# CajitaAbierta_v06_robotique.net
KiCad netlist of a schematic drawn in EAGLE
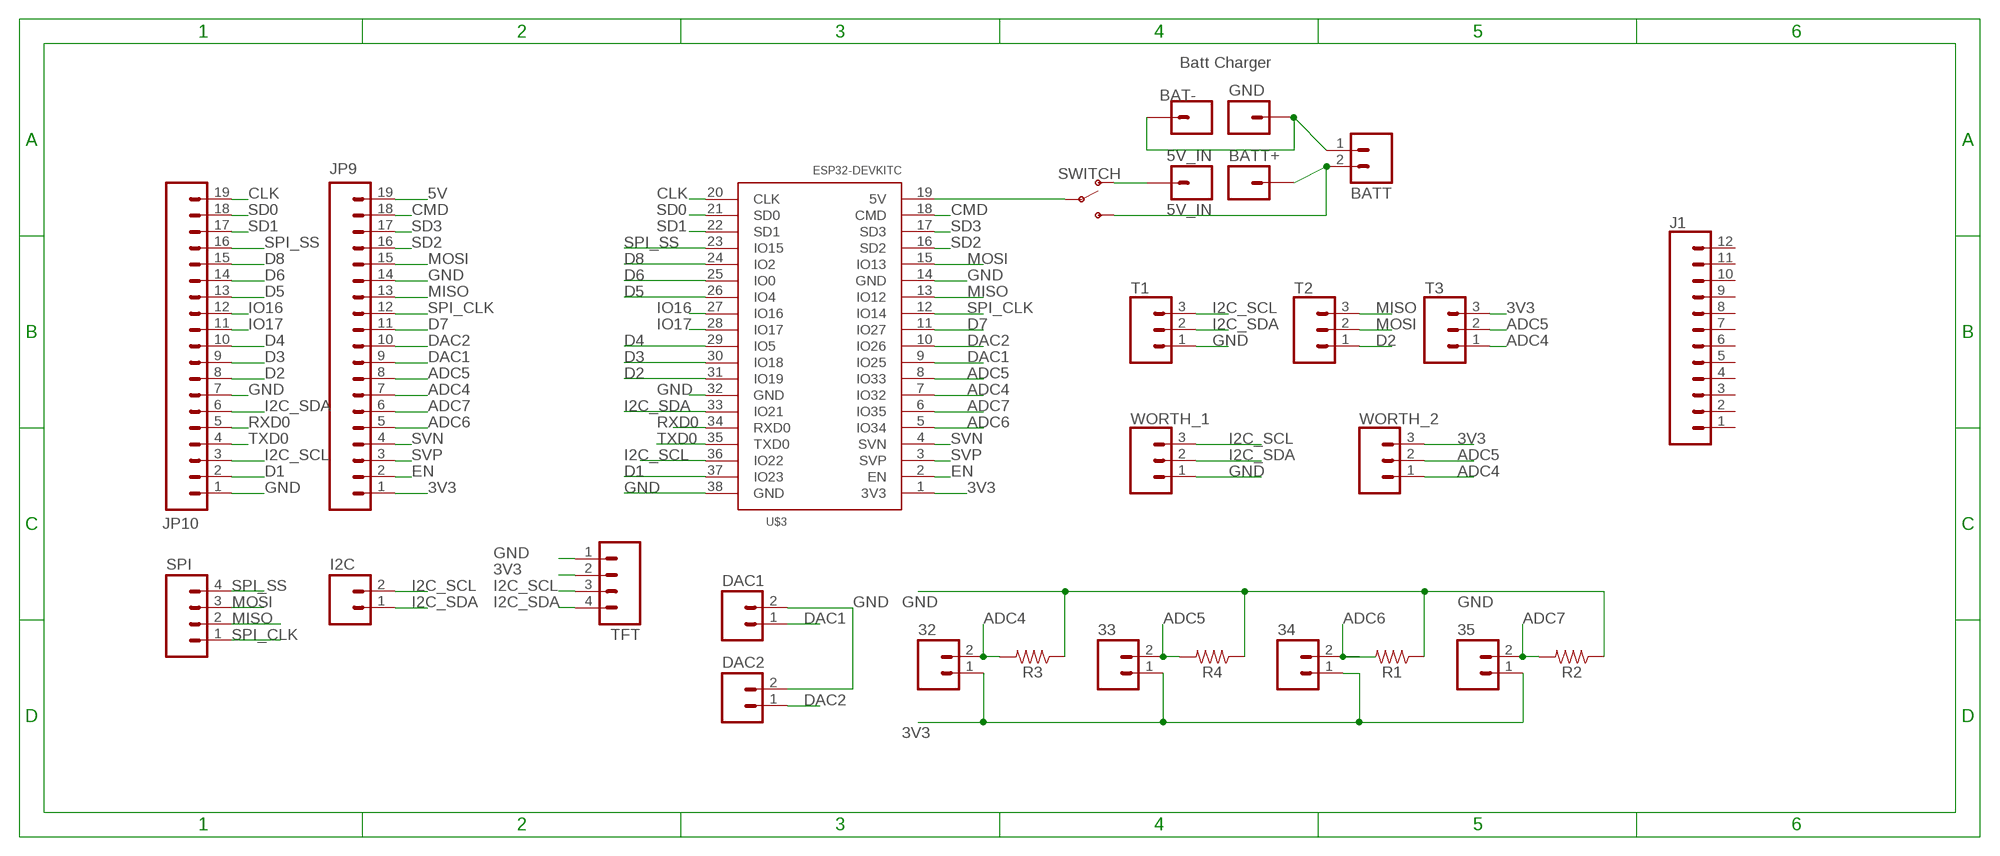
[diagram p0: schematic, sheet 1]

(export (version "E")
  (design (tool "Eeschema 10.0.6"))
  (components
    (comp (ref "5V_IN")
      (value "5V_IN")
      (footprint "eagle-import:1X01")
      (libsource (lib "eagle-import") (part "M01PTH"))
    )
    (comp (ref "32")
      (value "M02PTH")
      (footprint "eagle-import:1X02")
      (libsource (lib "eagle-import") (part "SparkFun-Connectors_6242394_M02PTH"))
    )
    (comp (ref "33")
      (value "M02PTH")
      (footprint "eagle-import:1X02")
      (libsource (lib "eagle-import") (part "SparkFun-Connectors_6242394_M02PTH"))
    )
    (comp (ref "34")
      (value "M02PTH")
      (footprint "eagle-import:1X02")
      (libsource (lib "eagle-import") (part "SparkFun-Connectors_6242394_M02PTH"))
    )
    (comp (ref "35")
      (value "M02PTH")
      (footprint "eagle-import:1X02")
      (libsource (lib "eagle-import") (part "SparkFun-Connectors_6242394_M02PTH"))
    )
    (comp (ref "BAT-")
      (value "M01PTH")
      (footprint "eagle-import:1X01")
      (libsource (lib "eagle-import") (part "M01PTH"))
    )
    (comp (ref "BATT")
      (value "M02LOCK_LONGPADS")
      (footprint "eagle-import:1X02_LOCK_LONGPADS")
      (libsource (lib "eagle-import") (part "M02LOCK_LONGPADS"))
    )
    (comp (ref "BATT+")
      (value "M01PTH")
      (footprint "eagle-import:1X01")
      (libsource (lib "eagle-import") (part "M01PTH"))
    )
    (comp (ref "DAC1")
      (value "M02PTH")
      (footprint "eagle-import:1X02")
      (libsource (lib "eagle-import") (part "SparkFun-Connectors_6242394_M02PTH"))
    )
    (comp (ref "DAC2")
      (value "M02PTH")
      (footprint "eagle-import:1X02")
      (libsource (lib "eagle-import") (part "SparkFun-Connectors_6242394_M02PTH"))
    )
    (comp (ref "GND")
      (value "Batt Charger")
      (footprint "eagle-import:1X01")
      (libsource (lib "eagle-import") (part "M01PTH"))
    )
    (comp (ref "I2C")
      (value "M02PTH")
      (footprint "eagle-import:1X02")
      (libsource (lib "eagle-import") (part "SparkFun-Connectors_6242394_M02PTH"))
    )
    (comp (ref "J1")
      (value "CONN_12NO_SILK")
      (footprint "eagle-import:1X12_NO_SILK")
      (libsource (lib "eagle-import") (part "CONN_12NO_SILK"))
    )
    (comp (ref "JP9")
      (value "M191X19")
      (footprint "eagle-import:1X19")
      (libsource (lib "eagle-import") (part "M191X19"))
    )
    (comp (ref "JP10")
      (value "M191X19")
      (footprint "eagle-import:1X19")
      (libsource (lib "eagle-import") (part "M191X19"))
    )
    (comp (ref "R1")
      (value "RESISTOR1206")
      (footprint "eagle-import:1206")
      (libsource (lib "eagle-import") (part "RESISTOR1206"))
    )
    (comp (ref "R2")
      (value "RESISTOR1206")
      (footprint "eagle-import:1206")
      (libsource (lib "eagle-import") (part "RESISTOR1206"))
    )
    (comp (ref "R3")
      (value "RESISTOR1206")
      (footprint "eagle-import:1206")
      (libsource (lib "eagle-import") (part "RESISTOR1206"))
    )
    (comp (ref "R4")
      (value "RESISTOR1206")
      (footprint "eagle-import:1206")
      (libsource (lib "eagle-import") (part "RESISTOR1206"))
    )
    (comp (ref "SPI")
      (value "M04PTH")
      (footprint "eagle-import:1X04")
      (libsource (lib "eagle-import") (part "M04PTH"))
    )
    (comp (ref "SWITCH")
      (value "SWITCH-SPDT-SMD-RIGHT-ANGLE")
      (footprint "eagle-import:SWITCH_SPST_SMD_A")
      (libsource (lib "eagle-import") (part "SWITCH-SPDT-SMD-RIGHT-ANGLE"))
    )
    (comp (ref "T1")
      (value "CONN_03SCREW-NS")
      (footprint "eagle-import:SCREWTERMINAL-3.5MM-3-NS")
      (libsource (lib "eagle-import") (part "CONN_03SCREW-NS"))
    )
    (comp (ref "T2")
      (value "CONN_03SCREW-NS")
      (footprint "eagle-import:SCREWTERMINAL-3.5MM-3-NS")
      (libsource (lib "eagle-import") (part "CONN_03SCREW-NS"))
    )
    (comp (ref "T3")
      (value "CONN_03SCREW-NS")
      (footprint "eagle-import:SCREWTERMINAL-3.5MM-3-NS")
      (libsource (lib "eagle-import") (part "CONN_03SCREW-NS"))
    )
    (comp (ref "TFT")
      (value "M04PTH")
      (footprint "eagle-import:1X04")
      (libsource (lib "eagle-import") (part "M04PTH"))
    )
    (comp (ref "U$3")
      (value "ESP32DEVKITC")
      (footprint "eagle-import:ESP32-DEVKITC")
      (libsource (lib "eagle-import") (part "ESP32DEVKITC"))
    )
    (comp (ref "WORTH_1")
      (value "CONN_03-SCREW-5MM")
      (footprint "eagle-import:SCREWTERMINAL-5MM-3")
      (libsource (lib "eagle-import") (part "CONN_03-SCREW-5MM"))
    )
    (comp (ref "WORTH_2")
      (value "CONN_03-SCREW-5MM")
      (footprint "eagle-import:SCREWTERMINAL-5MM-3")
      (libsource (lib "eagle-import") (part "CONN_03-SCREW-5MM"))
    )
  )
  (nets
    (net (code "1") (name "/3V3") (class "Default")
      (node (ref "32") (pin "1") (pinfunction "1_1") (pintype "passive"))
      (node (ref "33") (pin "1") (pinfunction "1_1") (pintype "passive"))
      (node (ref "34") (pin "1") (pinfunction "1_1") (pintype "passive"))
      (node (ref "35") (pin "1") (pinfunction "1_1") (pintype "passive"))
      (node (ref "JP9") (pin "1") (pinfunction "1_1") (pintype "passive"))
      (node (ref "T3") (pin "3") (pinfunction "3_3") (pintype "passive"))
      (node (ref "TFT") (pin "2") (pinfunction "2_2") (pintype "passive"))
      (node (ref "U$3") (pin "1") (pinfunction "3V3_1") (pintype "bidirectional"))
      (node (ref "WORTH_2") (pin "3") (pinfunction "3_3") (pintype "passive"))
    )
    (net (code "2") (name "/5V") (class "Default")
      (node (ref "JP9") (pin "19") (pinfunction "19_19") (pintype "passive"))
      (node (ref "SWITCH") (pin "2") (pinfunction "P_2") (pintype "passive"))
      (node (ref "U$3") (pin "19") (pinfunction "5V_19") (pintype "bidirectional"))
    )
    (net (code "3") (name "/ADC4") (class "Default")
      (node (ref "32") (pin "2") (pinfunction "2_2") (pintype "passive"))
      (node (ref "JP9") (pin "7") (pinfunction "7_7") (pintype "passive"))
      (node (ref "R3") (pin "2") (pinfunction "2_2") (pintype "passive"))
      (node (ref "T3") (pin "1") (pinfunction "1_1") (pintype "passive"))
      (node (ref "U$3") (pin "7") (pinfunction "IO32_7") (pintype "bidirectional"))
      (node (ref "WORTH_2") (pin "1") (pinfunction "1_1") (pintype "passive"))
    )
    (net (code "4") (name "/ADC5") (class "Default")
      (node (ref "33") (pin "2") (pinfunction "2_2") (pintype "passive"))
      (node (ref "JP9") (pin "8") (pinfunction "8_8") (pintype "passive"))
      (node (ref "R4") (pin "2") (pinfunction "2_2") (pintype "passive"))
      (node (ref "T3") (pin "2") (pinfunction "2_2") (pintype "passive"))
      (node (ref "U$3") (pin "8") (pinfunction "IO33_8") (pintype "bidirectional"))
      (node (ref "WORTH_2") (pin "2") (pinfunction "2_2") (pintype "passive"))
    )
    (net (code "5") (name "/ADC6") (class "Default")
      (node (ref "34") (pin "2") (pinfunction "2_2") (pintype "passive"))
      (node (ref "JP9") (pin "5") (pinfunction "5_5") (pintype "passive"))
      (node (ref "R1") (pin "2") (pinfunction "2_2") (pintype "passive"))
      (node (ref "U$3") (pin "5") (pinfunction "IO34_5") (pintype "bidirectional"))
    )
    (net (code "6") (name "/ADC7") (class "Default")
      (node (ref "35") (pin "2") (pinfunction "2_2") (pintype "passive"))
      (node (ref "JP9") (pin "6") (pinfunction "6_6") (pintype "passive"))
      (node (ref "R2") (pin "2") (pinfunction "2_2") (pintype "passive"))
      (node (ref "U$3") (pin "6") (pinfunction "IO35_6") (pintype "bidirectional"))
    )
    (net (code "7") (name "/CLK") (class "Default")
      (node (ref "JP10") (pin "19") (pinfunction "19_19") (pintype "passive"))
      (node (ref "U$3") (pin "20") (pinfunction "CLK_20") (pintype "bidirectional"))
    )
    (net (code "8") (name "/CMD") (class "Default")
      (node (ref "JP9") (pin "18") (pinfunction "18_18") (pintype "passive"))
      (node (ref "U$3") (pin "18") (pinfunction "CMD_18") (pintype "bidirectional"))
    )
    (net (code "9") (name "/D1") (class "Default")
      (node (ref "JP10") (pin "2") (pinfunction "2_2") (pintype "passive"))
      (node (ref "U$3") (pin "37") (pinfunction "IO23_37") (pintype "bidirectional"))
    )
    (net (code "10") (name "/D2") (class "Default")
      (node (ref "JP10") (pin "8") (pinfunction "8_8") (pintype "passive"))
      (node (ref "T2") (pin "1") (pinfunction "1_1") (pintype "passive"))
      (node (ref "U$3") (pin "31") (pinfunction "IO19_31") (pintype "bidirectional"))
    )
    (net (code "11") (name "/D3") (class "Default")
      (node (ref "JP10") (pin "9") (pinfunction "9_9") (pintype "passive"))
      (node (ref "U$3") (pin "30") (pinfunction "IO18_30") (pintype "bidirectional"))
    )
    (net (code "12") (name "/D4") (class "Default")
      (node (ref "JP10") (pin "10") (pinfunction "10_10") (pintype "passive"))
      (node (ref "U$3") (pin "29") (pinfunction "IO5_29") (pintype "bidirectional"))
    )
    (net (code "13") (name "/D5") (class "Default")
      (node (ref "JP10") (pin "13") (pinfunction "13_13") (pintype "passive"))
      (node (ref "U$3") (pin "26") (pinfunction "IO4_26") (pintype "bidirectional"))
    )
    (net (code "14") (name "/D6") (class "Default")
      (node (ref "JP10") (pin "14") (pinfunction "14_14") (pintype "passive"))
      (node (ref "U$3") (pin "25") (pinfunction "IO0_25") (pintype "bidirectional"))
    )
    (net (code "15") (name "/D7") (class "Default")
      (node (ref "JP9") (pin "11") (pinfunction "11_11") (pintype "passive"))
      (node (ref "U$3") (pin "11") (pinfunction "IO27_11") (pintype "bidirectional"))
    )
    (net (code "16") (name "/D8") (class "Default")
      (node (ref "JP10") (pin "15") (pinfunction "15_15") (pintype "passive"))
      (node (ref "U$3") (pin "24") (pinfunction "IO2_24") (pintype "bidirectional"))
    )
    (net (code "17") (name "/DAC1") (class "Default")
      (node (ref "DAC1") (pin "1") (pinfunction "1_1") (pintype "passive"))
      (node (ref "JP9") (pin "9") (pinfunction "9_9") (pintype "passive"))
      (node (ref "U$3") (pin "9") (pinfunction "IO25_9") (pintype "bidirectional"))
    )
    (net (code "18") (name "/DAC2") (class "Default")
      (node (ref "DAC2") (pin "1") (pinfunction "1_1") (pintype "passive"))
      (node (ref "JP9") (pin "10") (pinfunction "10_10") (pintype "passive"))
      (node (ref "U$3") (pin "10") (pinfunction "IO26_10") (pintype "bidirectional"))
    )
    (net (code "19") (name "/EN") (class "Default")
      (node (ref "JP9") (pin "2") (pinfunction "2_2") (pintype "passive"))
      (node (ref "U$3") (pin "2") (pinfunction "EN_2") (pintype "bidirectional"))
    )
    (net (code "20") (name "/GND") (class "Default")
      (node (ref "BAT-") (pin "1") (pinfunction "1_1") (pintype "passive"))
      (node (ref "BATT") (pin "1") (pinfunction "1_1") (pintype "passive"))
      (node (ref "DAC1") (pin "2") (pinfunction "2_2") (pintype "passive"))
      (node (ref "DAC2") (pin "2") (pinfunction "2_2") (pintype "passive"))
      (node (ref "GND") (pin "1") (pinfunction "1_1") (pintype "passive"))
      (node (ref "JP10") (pin "1") (pinfunction "1_1") (pintype "passive"))
      (node (ref "JP10") (pin "7") (pinfunction "7_7") (pintype "passive"))
      (node (ref "JP9") (pin "14") (pinfunction "14_14") (pintype "passive"))
      (node (ref "R1") (pin "1") (pinfunction "1_1") (pintype "passive"))
      (node (ref "R2") (pin "1") (pinfunction "1_1") (pintype "passive"))
      (node (ref "R3") (pin "1") (pinfunction "1_1") (pintype "passive"))
      (node (ref "R4") (pin "1") (pinfunction "1_1") (pintype "passive"))
      (node (ref "T1") (pin "1") (pinfunction "1_1") (pintype "passive"))
      (node (ref "TFT") (pin "1") (pinfunction "1_1") (pintype "passive"))
      (node (ref "U$3") (pin "14") (pinfunction "GND_14") (pintype "bidirectional"))
      (node (ref "U$3") (pin "32") (pinfunction "GND_32") (pintype "bidirectional"))
      (node (ref "U$3") (pin "38") (pinfunction "GND_38") (pintype "bidirectional"))
      (node (ref "WORTH_1") (pin "1") (pinfunction "1_1") (pintype "passive"))
    )
    (net (code "21") (name "/I2C_SCL") (class "Default")
      (node (ref "I2C") (pin "2") (pinfunction "2_2") (pintype "passive"))
      (node (ref "JP10") (pin "3") (pinfunction "3_3") (pintype "passive"))
      (node (ref "T1") (pin "3") (pinfunction "3_3") (pintype "passive"))
      (node (ref "TFT") (pin "3") (pinfunction "3_3") (pintype "passive"))
      (node (ref "U$3") (pin "36") (pinfunction "IO22_36") (pintype "bidirectional"))
      (node (ref "WORTH_1") (pin "3") (pinfunction "3_3") (pintype "passive"))
    )
    (net (code "22") (name "/I2C_SDA") (class "Default")
      (node (ref "I2C") (pin "1") (pinfunction "1_1") (pintype "passive"))
      (node (ref "JP10") (pin "6") (pinfunction "6_6") (pintype "passive"))
      (node (ref "T1") (pin "2") (pinfunction "2_2") (pintype "passive"))
      (node (ref "TFT") (pin "4") (pinfunction "4_4") (pintype "passive"))
      (node (ref "U$3") (pin "33") (pinfunction "IO21_33") (pintype "bidirectional"))
      (node (ref "WORTH_1") (pin "2") (pinfunction "2_2") (pintype "passive"))
    )
    (net (code "23") (name "/IO16") (class "Default")
      (node (ref "JP10") (pin "12") (pinfunction "12_12") (pintype "passive"))
      (node (ref "U$3") (pin "27") (pinfunction "IO16_27") (pintype "bidirectional"))
    )
    (net (code "24") (name "/IO17") (class "Default")
      (node (ref "JP10") (pin "11") (pinfunction "11_11") (pintype "passive"))
      (node (ref "U$3") (pin "28") (pinfunction "IO17_28") (pintype "bidirectional"))
    )
    (net (code "25") (name "/MISO") (class "Default")
      (node (ref "JP9") (pin "13") (pinfunction "13_13") (pintype "passive"))
      (node (ref "SPI") (pin "2") (pinfunction "2_2") (pintype "passive"))
      (node (ref "T2") (pin "3") (pinfunction "3_3") (pintype "passive"))
      (node (ref "U$3") (pin "13") (pinfunction "IO12_13") (pintype "bidirectional"))
    )
    (net (code "26") (name "/MOSI") (class "Default")
      (node (ref "JP9") (pin "15") (pinfunction "15_15") (pintype "passive"))
      (node (ref "SPI") (pin "3") (pinfunction "3_3") (pintype "passive"))
      (node (ref "T2") (pin "2") (pinfunction "2_2") (pintype "passive"))
      (node (ref "U$3") (pin "15") (pinfunction "IO13_15") (pintype "bidirectional"))
    )
    (net (code "27") (name "/RXD0") (class "Default")
      (node (ref "JP10") (pin "5") (pinfunction "5_5") (pintype "passive"))
      (node (ref "U$3") (pin "34") (pinfunction "RXD0_34") (pintype "bidirectional"))
    )
    (net (code "28") (name "/SD0") (class "Default")
      (node (ref "JP10") (pin "18") (pinfunction "18_18") (pintype "passive"))
      (node (ref "U$3") (pin "21") (pinfunction "SD0_21") (pintype "bidirectional"))
    )
    (net (code "29") (name "/SD1") (class "Default")
      (node (ref "JP10") (pin "17") (pinfunction "17_17") (pintype "passive"))
      (node (ref "U$3") (pin "22") (pinfunction "SD1_22") (pintype "bidirectional"))
    )
    (net (code "30") (name "/SD2") (class "Default")
      (node (ref "JP9") (pin "16") (pinfunction "16_16") (pintype "passive"))
      (node (ref "U$3") (pin "16") (pinfunction "SD2_16") (pintype "bidirectional"))
    )
    (net (code "31") (name "/SD3") (class "Default")
      (node (ref "JP9") (pin "17") (pinfunction "17_17") (pintype "passive"))
      (node (ref "U$3") (pin "17") (pinfunction "SD3_17") (pintype "bidirectional"))
    )
    (net (code "32") (name "/SPI_CLK") (class "Default")
      (node (ref "JP9") (pin "12") (pinfunction "12_12") (pintype "passive"))
      (node (ref "SPI") (pin "1") (pinfunction "1_1") (pintype "passive"))
      (node (ref "U$3") (pin "12") (pinfunction "IO14_12") (pintype "bidirectional"))
    )
    (net (code "33") (name "/SPI_SS") (class "Default")
      (node (ref "JP10") (pin "16") (pinfunction "16_16") (pintype "passive"))
      (node (ref "SPI") (pin "4") (pinfunction "4_4") (pintype "passive"))
      (node (ref "U$3") (pin "23") (pinfunction "IO15_23") (pintype "bidirectional"))
    )
    (net (code "34") (name "/SVN") (class "Default")
      (node (ref "JP9") (pin "4") (pinfunction "4_4") (pintype "passive"))
      (node (ref "U$3") (pin "4") (pinfunction "SVN_4") (pintype "bidirectional"))
    )
    (net (code "35") (name "/SVP") (class "Default")
      (node (ref "JP9") (pin "3") (pinfunction "3_3") (pintype "passive"))
      (node (ref "U$3") (pin "3") (pinfunction "SVP_3") (pintype "bidirectional"))
    )
    (net (code "36") (name "/TXD0") (class "Default")
      (node (ref "JP10") (pin "4") (pinfunction "4_4") (pintype "passive"))
      (node (ref "U$3") (pin "35") (pinfunction "TXD0_35") (pintype "bidirectional"))
    )
    (net (code "37") (name "Net-(SWITCH-O)") (class "Default")
      (node (ref "5V_IN") (pin "1") (pinfunction "1_1") (pintype "passive"))
      (node (ref "SWITCH") (pin "1") (pinfunction "O_1") (pintype "passive"))
    )
    (net (code "38") (name "Net-(SWITCH-S)") (class "Default")
      (node (ref "BATT") (pin "2") (pinfunction "2_2") (pintype "passive"))
      (node (ref "BATT+") (pin "1") (pinfunction "1_1") (pintype "passive"))
      (node (ref "SWITCH") (pin "3") (pinfunction "S_3") (pintype "passive"))
    )
    (net (code "39") (name "unconnected-(J1-Pad1)") (class "Default")
      (node (ref "J1") (pin "1") (pinfunction "1_1") (pintype "passive"))
    )
    (net (code "40") (name "unconnected-(J1-Pad2)") (class "Default")
      (node (ref "J1") (pin "2") (pinfunction "2_2") (pintype "passive"))
    )
    (net (code "41") (name "unconnected-(J1-Pad3)") (class "Default")
      (node (ref "J1") (pin "3") (pinfunction "3_3") (pintype "passive"))
    )
    (net (code "42") (name "unconnected-(J1-Pad4)") (class "Default")
      (node (ref "J1") (pin "4") (pinfunction "4_4") (pintype "passive"))
    )
    (net (code "43") (name "unconnected-(J1-Pad5)") (class "Default")
      (node (ref "J1") (pin "5") (pinfunction "5_5") (pintype "passive"))
    )
    (net (code "44") (name "unconnected-(J1-Pad6)") (class "Default")
      (node (ref "J1") (pin "6") (pinfunction "6_6") (pintype "passive"))
    )
    (net (code "45") (name "unconnected-(J1-Pad7)") (class "Default")
      (node (ref "J1") (pin "7") (pinfunction "7_7") (pintype "passive"))
    )
    (net (code "46") (name "unconnected-(J1-Pad8)") (class "Default")
      (node (ref "J1") (pin "8") (pinfunction "8_8") (pintype "passive"))
    )
    (net (code "47") (name "unconnected-(J1-Pad9)") (class "Default")
      (node (ref "J1") (pin "9") (pinfunction "9_9") (pintype "passive"))
    )
    (net (code "48") (name "unconnected-(J1-Pad10)") (class "Default")
      (node (ref "J1") (pin "10") (pinfunction "10_10") (pintype "passive"))
    )
    (net (code "49") (name "unconnected-(J1-Pad11)") (class "Default")
      (node (ref "J1") (pin "11") (pinfunction "11_11") (pintype "passive"))
    )
    (net (code "50") (name "unconnected-(J1-Pad12)") (class "Default")
      (node (ref "J1") (pin "12") (pinfunction "12_12") (pintype "passive"))
    )
  )
)
